# 1_NZPP.net
KiCad netlist of a schematic drawn in Altium Designer
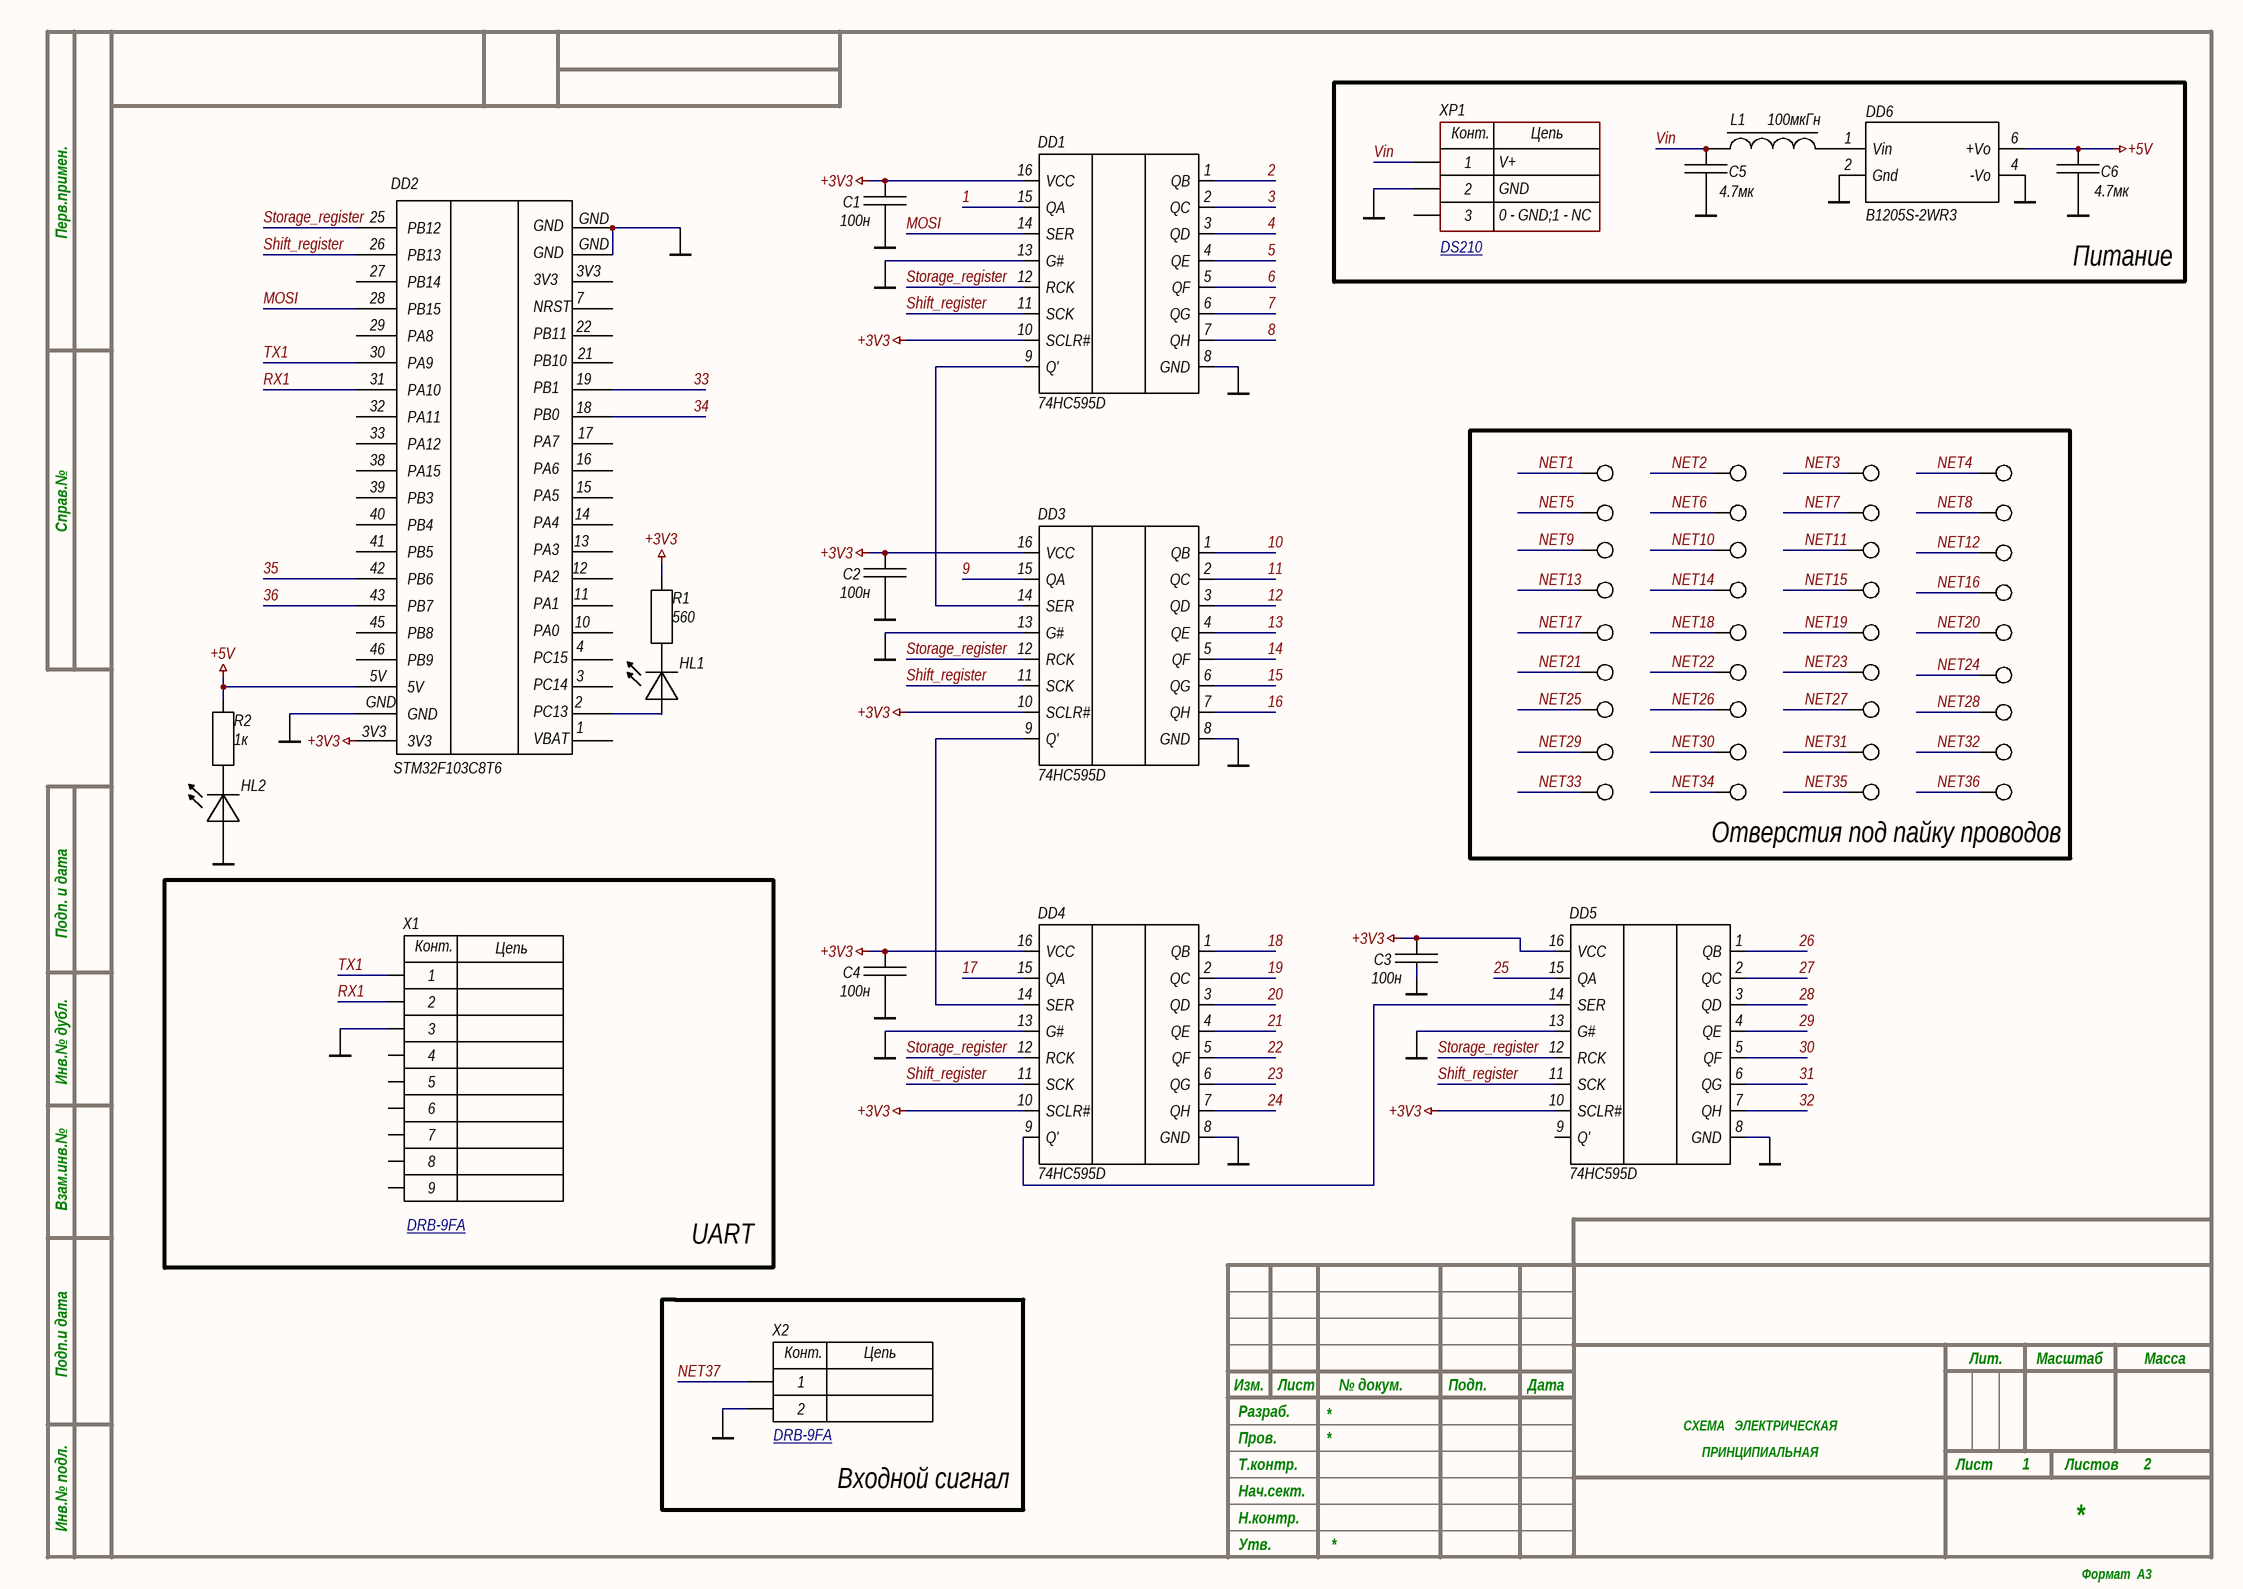
[diagram p0: 1.NZPP.SchDoc]

(export (version "E")
  (design (tool "Eeschema 10.0.6"))
  (components
    (comp (ref "*") (value "Point") (footprint "Point") (libsource (lib "Schlib1") (part "Point")))
    (comp (ref "*1") (value "Point") (footprint "Point") (libsource (lib "Schlib1") (part "Point")))
    (comp (ref "*2") (value "Point") (footprint "Point") (libsource (lib "Schlib1") (part "Point")))
    (comp (ref "*3") (value "Point") (footprint "Point") (libsource (lib "Schlib1") (part "Point")))
    (comp (ref "*4") (value "Point") (footprint "Point") (libsource (lib "Schlib1") (part "Point")))
    (comp (ref "*5") (value "Point") (footprint "Point") (libsource (lib "Schlib1") (part "Point")))
    (comp (ref "*6") (value "Point") (footprint "Point") (libsource (lib "Schlib1") (part "Point")))
    (comp (ref "*7") (value "Point") (footprint "Point") (libsource (lib "Schlib1") (part "Point")))
    (comp (ref "*8") (value "Point") (footprint "Point") (libsource (lib "Schlib1") (part "Point")))
    (comp (ref "*9") (value "Point") (footprint "Point") (libsource (lib "Schlib1") (part "Point")))
    (comp (ref "*10") (value "Point") (footprint "Point") (libsource (lib "Schlib1") (part "Point")))
    (comp (ref "*11") (value "Point") (footprint "Point") (libsource (lib "Schlib1") (part "Point")))
    (comp (ref "*12") (value "Point") (footprint "Point") (libsource (lib "Schlib1") (part "Point")))
    (comp (ref "*13") (value "Point") (footprint "Point") (libsource (lib "Schlib1") (part "Point")))
    (comp (ref "*14") (value "Point") (footprint "Point") (libsource (lib "Schlib1") (part "Point")))
    (comp (ref "*15") (value "Point") (footprint "Point") (libsource (lib "Schlib1") (part "Point")))
    (comp (ref "*16") (value "Point") (footprint "Point") (libsource (lib "Schlib1") (part "Point")))
    (comp (ref "*17") (value "Point") (footprint "Point") (libsource (lib "Schlib1") (part "Point")))
    (comp (ref "*18") (value "Point") (footprint "Point") (libsource (lib "Schlib1") (part "Point")))
    (comp (ref "*19") (value "Point") (footprint "Point") (libsource (lib "Schlib1") (part "Point")))
    (comp (ref "*20") (value "Point") (footprint "Point") (libsource (lib "Schlib1") (part "Point")))
    (comp (ref "*21") (value "Point") (footprint "Point") (libsource (lib "Schlib1") (part "Point")))
    (comp (ref "*22") (value "Point") (footprint "Point") (libsource (lib "Schlib1") (part "Point")))
    (comp (ref "*23") (value "Point") (footprint "Point") (libsource (lib "Schlib1") (part "Point")))
    (comp (ref "*24") (value "Point") (footprint "Point") (libsource (lib "Schlib1") (part "Point")))
    (comp (ref "*25") (value "Point") (footprint "Point") (libsource (lib "Schlib1") (part "Point")))
    (comp (ref "*26") (value "Point") (footprint "Point") (libsource (lib "Schlib1") (part "Point")))
    (comp (ref "*27") (value "Point") (footprint "Point") (libsource (lib "Schlib1") (part "Point")))
    (comp (ref "*28") (value "Point") (footprint "Point") (libsource (lib "Schlib1") (part "Point")))
    (comp (ref "*29") (value "Point") (footprint "Point") (libsource (lib "Schlib1") (part "Point")))
    (comp (ref "*30") (value "Point") (footprint "Point") (libsource (lib "Schlib1") (part "Point")))
    (comp (ref "*31") (value "Point") (footprint "Point") (libsource (lib "Schlib1") (part "Point")))
    (comp (ref "*32") (value "Point") (footprint "Point") (libsource (lib "Schlib1") (part "Point")))
    (comp (ref "*33") (value "Point") (footprint "Point") (libsource (lib "Schlib1") (part "Point")))
    (comp (ref "*34") (value "Point") (footprint "Point") (libsource (lib "Schlib1") (part "Point")))
    (comp (ref "*35") (value "Point") (footprint "Point") (libsource (lib "Schlib1") (part "Point")))
    (comp (ref "C1")
      (value "100н")
      (footprint "CAP: 0805")
      (libsource (lib "capacitor") (part "Ceramic_0805"))
    )
    (comp (ref "C2")
      (value "100н")
      (footprint "CAP: 0805")
      (libsource (lib "capacitor") (part "Ceramic_0805"))
    )
    (comp (ref "C3")
      (value "100н")
      (footprint "CAP: 0805")
      (libsource (lib "capacitor") (part "Ceramic_0805"))
    )
    (comp (ref "C4")
      (value "100н")
      (footprint "CAP: 0805")
      (libsource (lib "capacitor") (part "Ceramic_0805"))
    )
    (comp (ref "C5")
      (value "4.7мк")
      (footprint "CAP: 0805")
      (libsource (lib "capacitor") (part "Ceramic_0805"))
    )
    (comp (ref "C6")
      (value "4.7мк")
      (footprint "CAP: 0805")
      (libsource (lib "capacitor") (part "Ceramic_0805"))
    )
    (comp (ref "DD1") (value "74HC595D") (footprint "74HC595D") (libsource (lib "") (part "74HC595D_1")))
    (comp (ref "DD2")
      (value "STM32F103C8T6")
      (footprint "STM32F103C8T6 - duplicate")
      (libsource (lib "Schlib1") (part "STM32F103"))
    )
    (comp (ref "DD3") (value "74HC595D") (footprint "74HC595D") (libsource (lib "Schlib1") (part "74HC595D")))
    (comp (ref "DD4") (value "74HC595D") (footprint "74HC595D") (libsource (lib "Schlib1") (part "74HC595D")))
    (comp (ref "DD5") (value "74HC595D") (footprint "74HC595D") (libsource (lib "Schlib1") (part "74HC595D")))
    (comp (ref "DD6")
      (value "B1205S-2WR3")
      (footprint "B1205S-2WR3")
      (libsource (lib "Schlib1") (part "B1205S-2WR3"))
    )
    (comp (ref "HL1") (value "GNL-3012HD") (footprint "led") (libsource (lib "Schlib1") (part "LED")))
    (comp (ref "HL2") (value "GNL-3012HD") (footprint "led") (libsource (lib "Schlib1") (part "LED")))
    (comp (ref "L1")
      (value "100мкГн")
      (footprint "100мкГн")
      (libsource (lib "Schlib1") (part "Дроссель 100мкГн CD43-101K"))
    )
    (comp (ref "R1")
      (value "560")
      (footprint "RES: 0805")
      (libsource (lib "resistor") (part "Resistor_0805"))
    )
    (comp (ref "R2") (value "1к") (footprint "RES: 0805") (libsource (lib "resistor") (part "Resistor_0805")))
    (comp (ref "X1") (value "DRB-9FA") (footprint "CON: DB-9F") (libsource (lib "Schlib1") (part "DRB-9FA")))
    (comp (ref "X2")
      (value "SMA-KWHD")
      (footprint "CON: SMA-KWHD")
      (libsource (lib "Schlib1") (part "Connector_terminal_2pin"))
    )
    (comp (ref "XP1") (value "DS210") (footprint "CON: DS210") (libsource (lib "Schlib1") (part "DS210")))
  )
  (nets
    (net (code "1") (name "+3V3") (class "Default")
      (node (ref "C1") (pin "2") (pinfunction "2_2") (pintype "passive"))
      (node (ref "C2") (pin "2") (pinfunction "2_2") (pintype "passive"))
      (node (ref "C3") (pin "2") (pinfunction "2_2") (pintype "passive"))
      (node (ref "C4") (pin "2") (pinfunction "2_2") (pintype "passive"))
      (node (ref "DD1") (pin "10") (pinfunction "SCLR#_10") (pintype "passive"))
      (node (ref "DD1") (pin "16") (pinfunction "VCC_16") (pintype "passive"))
      (node (ref "DD2") (pin "A2") (pinfunction "3V3_A2") (pintype "passive"))
      (node (ref "DD3") (pin "10") (pinfunction "SCLR#_10") (pintype "passive"))
      (node (ref "DD3") (pin "16") (pinfunction "VCC_16") (pintype "passive"))
      (node (ref "DD4") (pin "10") (pinfunction "SCLR#_10") (pintype "passive"))
      (node (ref "DD4") (pin "16") (pinfunction "VCC_16") (pintype "passive"))
      (node (ref "DD5") (pin "10") (pinfunction "SCLR#_10") (pintype "passive"))
      (node (ref "DD5") (pin "16") (pinfunction "VCC_16") (pintype "passive"))
      (node (ref "R1") (pin "2") (pinfunction "2_2") (pintype "passive"))
    )
    (net (code "2") (name "+5V") (class "Default")
      (node (ref "C6") (pin "2") (pinfunction "2_2") (pintype "passive"))
      (node (ref "DD2") (pin "5V") (pinfunction "5V_5V") (pintype "passive"))
      (node (ref "DD6") (pin "6") (pinfunction "+Vo_6") (pintype "passive"))
      (node (ref "R2") (pin "2") (pinfunction "2_2") (pintype "passive"))
    )
    (net (code "3") (name "/1") (class "Default")
      (node (ref "DD1") (pin "15") (pinfunction "QA_15") (pintype "passive"))
    )
    (net (code "4") (name "/2") (class "Default")
      (node (ref "DD1") (pin "1") (pinfunction "QB_1") (pintype "passive"))
    )
    (net (code "5") (name "/3") (class "Default")
      (node (ref "DD1") (pin "2") (pinfunction "QC_2") (pintype "passive"))
    )
    (net (code "6") (name "/4") (class "Default")
      (node (ref "DD1") (pin "3") (pinfunction "QD_3") (pintype "passive"))
    )
    (net (code "7") (name "/5") (class "Default")
      (node (ref "DD1") (pin "4") (pinfunction "QE_4") (pintype "passive"))
    )
    (net (code "8") (name "/6") (class "Default")
      (node (ref "DD1") (pin "5") (pinfunction "QF_5") (pintype "passive"))
    )
    (net (code "9") (name "/7") (class "Default")
      (node (ref "DD1") (pin "6") (pinfunction "QG_6") (pintype "passive"))
    )
    (net (code "10") (name "/8") (class "Default")
      (node (ref "DD1") (pin "7") (pinfunction "QH_7") (pintype "passive"))
    )
    (net (code "11") (name "/9") (class "Default")
      (node (ref "DD3") (pin "15") (pinfunction "QA_15") (pintype "passive"))
    )
    (net (code "12") (name "/10") (class "Default")
      (node (ref "DD3") (pin "1") (pinfunction "QB_1") (pintype "passive"))
    )
    (net (code "13") (name "/11") (class "Default")
      (node (ref "DD3") (pin "2") (pinfunction "QC_2") (pintype "passive"))
    )
    (net (code "14") (name "/12") (class "Default")
      (node (ref "DD3") (pin "3") (pinfunction "QD_3") (pintype "passive"))
    )
    (net (code "15") (name "/13") (class "Default")
      (node (ref "DD3") (pin "4") (pinfunction "QE_4") (pintype "passive"))
    )
    (net (code "16") (name "/14") (class "Default")
      (node (ref "DD3") (pin "5") (pinfunction "QF_5") (pintype "passive"))
    )
    (net (code "17") (name "/15") (class "Default")
      (node (ref "DD3") (pin "6") (pinfunction "QG_6") (pintype "passive"))
    )
    (net (code "18") (name "/16") (class "Default")
      (node (ref "DD3") (pin "7") (pinfunction "QH_7") (pintype "passive"))
    )
    (net (code "19") (name "/17") (class "Default")
      (node (ref "DD4") (pin "15") (pinfunction "QA_15") (pintype "passive"))
    )
    (net (code "20") (name "/18") (class "Default")
      (node (ref "DD4") (pin "1") (pinfunction "QB_1") (pintype "passive"))
    )
    (net (code "21") (name "/19") (class "Default")
      (node (ref "DD4") (pin "2") (pinfunction "QC_2") (pintype "passive"))
    )
    (net (code "22") (name "/20") (class "Default")
      (node (ref "DD4") (pin "3") (pinfunction "QD_3") (pintype "passive"))
    )
    (net (code "23") (name "/21") (class "Default")
      (node (ref "DD4") (pin "4") (pinfunction "QE_4") (pintype "passive"))
    )
    (net (code "24") (name "/22") (class "Default")
      (node (ref "DD4") (pin "5") (pinfunction "QF_5") (pintype "passive"))
    )
    (net (code "25") (name "/23") (class "Default")
      (node (ref "DD4") (pin "6") (pinfunction "QG_6") (pintype "passive"))
    )
    (net (code "26") (name "/24") (class "Default")
      (node (ref "DD4") (pin "7") (pinfunction "QH_7") (pintype "passive"))
    )
    (net (code "27") (name "/25") (class "Default")
      (node (ref "DD5") (pin "15") (pinfunction "QA_15") (pintype "passive"))
    )
    (net (code "28") (name "/26") (class "Default")
      (node (ref "DD5") (pin "1") (pinfunction "QB_1") (pintype "passive"))
    )
    (net (code "29") (name "/27") (class "Default")
      (node (ref "DD5") (pin "2") (pinfunction "QC_2") (pintype "passive"))
    )
    (net (code "30") (name "/28") (class "Default")
      (node (ref "DD5") (pin "3") (pinfunction "QD_3") (pintype "passive"))
    )
    (net (code "31") (name "/29") (class "Default")
      (node (ref "DD5") (pin "4") (pinfunction "QE_4") (pintype "passive"))
    )
    (net (code "32") (name "/30") (class "Default")
      (node (ref "DD5") (pin "5") (pinfunction "QF_5") (pintype "passive"))
    )
    (net (code "33") (name "/31") (class "Default")
      (node (ref "DD5") (pin "6") (pinfunction "QG_6") (pintype "passive"))
    )
    (net (code "34") (name "/32") (class "Default")
      (node (ref "DD5") (pin "7") (pinfunction "QH_7") (pintype "passive"))
    )
    (net (code "35") (name "/33") (class "Default")
      (node (ref "DD2") (pin "19") (pinfunction "PB1_19") (pintype "passive"))
    )
    (net (code "36") (name "/34") (class "Default")
      (node (ref "DD2") (pin "18") (pinfunction "PB0_18") (pintype "passive"))
    )
    (net (code "37") (name "/35") (class "Default")
      (node (ref "DD2") (pin "42") (pinfunction "PB6_42") (pintype "passive"))
    )
    (net (code "38") (name "/36") (class "Default")
      (node (ref "DD2") (pin "43") (pinfunction "PB7_43") (pintype "passive"))
    )
    (net (code "39") (name "/MOSI") (class "Default")
      (node (ref "DD1") (pin "14") (pinfunction "SER_14") (pintype "passive"))
      (node (ref "DD2") (pin "28") (pinfunction "PB15_28") (pintype "passive"))
    )
    (net (code "40") (name "/NET1") (class "Default")
      (node (ref "*") (pin "1") (pinfunction "4_1") (pintype "passive"))
    )
    (net (code "41") (name "/NET2") (class "Default")
      (node (ref "*1") (pin "1") (pinfunction "4_1") (pintype "passive"))
    )
    (net (code "42") (name "/NET3") (class "Default")
      (node (ref "*2") (pin "1") (pinfunction "4_1") (pintype "passive"))
    )
    (net (code "43") (name "/NET4") (class "Default")
      (node (ref "*3") (pin "1") (pinfunction "4_1") (pintype "passive"))
    )
    (net (code "44") (name "/NET5") (class "Default")
      (node (ref "*4") (pin "1") (pinfunction "4_1") (pintype "passive"))
    )
    (net (code "45") (name "/NET6") (class "Default")
      (node (ref "*5") (pin "1") (pinfunction "4_1") (pintype "passive"))
    )
    (net (code "46") (name "/NET7") (class "Default")
      (node (ref "*6") (pin "1") (pinfunction "4_1") (pintype "passive"))
    )
    (net (code "47") (name "/NET8") (class "Default")
      (node (ref "*7") (pin "1") (pinfunction "4_1") (pintype "passive"))
    )
    (net (code "48") (name "/NET9") (class "Default")
      (node (ref "*8") (pin "1") (pinfunction "4_1") (pintype "passive"))
    )
    (net (code "49") (name "/NET10") (class "Default")
      (node (ref "*9") (pin "1") (pinfunction "4_1") (pintype "passive"))
    )
    (net (code "50") (name "/NET11") (class "Default")
      (node (ref "*10") (pin "1") (pinfunction "4_1") (pintype "passive"))
    )
    (net (code "51") (name "/NET12") (class "Default")
      (node (ref "*11") (pin "1") (pinfunction "4_1") (pintype "passive"))
    )
    (net (code "52") (name "/NET13") (class "Default")
      (node (ref "*12") (pin "1") (pinfunction "4_1") (pintype "passive"))
    )
    (net (code "53") (name "/NET14") (class "Default")
      (node (ref "*13") (pin "1") (pinfunction "4_1") (pintype "passive"))
    )
    (net (code "54") (name "/NET15") (class "Default")
      (node (ref "*14") (pin "1") (pinfunction "4_1") (pintype "passive"))
    )
    (net (code "55") (name "/NET16") (class "Default")
      (node (ref "*15") (pin "1") (pinfunction "4_1") (pintype "passive"))
    )
    (net (code "56") (name "/NET17") (class "Default")
      (node (ref "*16") (pin "1") (pinfunction "4_1") (pintype "passive"))
    )
    (net (code "57") (name "/NET18") (class "Default")
      (node (ref "*17") (pin "1") (pinfunction "4_1") (pintype "passive"))
    )
    (net (code "58") (name "/NET19") (class "Default")
      (node (ref "*18") (pin "1") (pinfunction "4_1") (pintype "passive"))
    )
    (net (code "59") (name "/NET20") (class "Default")
      (node (ref "*19") (pin "1") (pinfunction "4_1") (pintype "passive"))
    )
    (net (code "60") (name "/NET21") (class "Default")
      (node (ref "*20") (pin "1") (pinfunction "4_1") (pintype "passive"))
    )
    (net (code "61") (name "/NET22") (class "Default")
      (node (ref "*21") (pin "1") (pinfunction "4_1") (pintype "passive"))
    )
    (net (code "62") (name "/NET23") (class "Default")
      (node (ref "*22") (pin "1") (pinfunction "4_1") (pintype "passive"))
    )
    (net (code "63") (name "/NET24") (class "Default")
      (node (ref "*23") (pin "1") (pinfunction "4_1") (pintype "passive"))
    )
    (net (code "64") (name "/NET25") (class "Default")
      (node (ref "*24") (pin "1") (pinfunction "4_1") (pintype "passive"))
    )
    (net (code "65") (name "/NET26") (class "Default")
      (node (ref "*25") (pin "1") (pinfunction "4_1") (pintype "passive"))
    )
    (net (code "66") (name "/NET27") (class "Default")
      (node (ref "*26") (pin "1") (pinfunction "4_1") (pintype "passive"))
    )
    (net (code "67") (name "/NET28") (class "Default")
      (node (ref "*27") (pin "1") (pinfunction "4_1") (pintype "passive"))
    )
    (net (code "68") (name "/NET29") (class "Default")
      (node (ref "*28") (pin "1") (pinfunction "4_1") (pintype "passive"))
    )
    (net (code "69") (name "/NET30") (class "Default")
      (node (ref "*29") (pin "1") (pinfunction "4_1") (pintype "passive"))
    )
    (net (code "70") (name "/NET31") (class "Default")
      (node (ref "*30") (pin "1") (pinfunction "4_1") (pintype "passive"))
    )
    (net (code "71") (name "/NET32") (class "Default")
      (node (ref "*31") (pin "1") (pinfunction "4_1") (pintype "passive"))
    )
    (net (code "72") (name "/NET33") (class "Default")
      (node (ref "*32") (pin "1") (pinfunction "4_1") (pintype "passive"))
    )
    (net (code "73") (name "/NET34") (class "Default")
      (node (ref "*33") (pin "1") (pinfunction "4_1") (pintype "passive"))
    )
    (net (code "74") (name "/NET35") (class "Default")
      (node (ref "*34") (pin "1") (pinfunction "4_1") (pintype "passive"))
    )
    (net (code "75") (name "/NET36") (class "Default")
      (node (ref "*35") (pin "1") (pinfunction "4_1") (pintype "passive"))
    )
    (net (code "76") (name "/NET37") (class "Default")
      (node (ref "X2") (pin "1") (pinfunction "1_1") (pintype "passive"))
    )
    (net (code "77") (name "/RX1") (class "Default")
      (node (ref "DD2") (pin "31") (pinfunction "PA10_31") (pintype "passive"))
      (node (ref "X1") (pin "2") (pinfunction "2_2") (pintype "passive"))
    )
    (net (code "78") (name "/Shift_register") (class "Default")
      (node (ref "DD1") (pin "11") (pinfunction "SCK_11") (pintype "passive"))
      (node (ref "DD2") (pin "26") (pinfunction "PB13_26") (pintype "passive"))
      (node (ref "DD3") (pin "11") (pinfunction "SCK_11") (pintype "passive"))
      (node (ref "DD4") (pin "11") (pinfunction "SCK_11") (pintype "passive"))
      (node (ref "DD5") (pin "11") (pinfunction "SCK_11") (pintype "passive"))
    )
    (net (code "79") (name "/Storage_register") (class "Default")
      (node (ref "DD1") (pin "12") (pinfunction "RCK_12") (pintype "passive"))
      (node (ref "DD2") (pin "25") (pinfunction "PB12_25") (pintype "passive"))
      (node (ref "DD3") (pin "12") (pinfunction "RCK_12") (pintype "passive"))
      (node (ref "DD4") (pin "12") (pinfunction "RCK_12") (pintype "passive"))
      (node (ref "DD5") (pin "12") (pinfunction "RCK_12") (pintype "passive"))
    )
    (net (code "80") (name "/TX1") (class "Default")
      (node (ref "DD2") (pin "30") (pinfunction "PA9_30") (pintype "passive"))
      (node (ref "X1") (pin "1") (pinfunction "1_1") (pintype "passive"))
    )
    (net (code "81") (name "/Vin") (class "Default")
      (node (ref "C5") (pin "2") (pinfunction "2_2") (pintype "passive"))
      (node (ref "L1") (pin "1") (pinfunction "1_1") (pintype "passive"))
      (node (ref "XP1") (pin "1") (pinfunction "1_1") (pintype "passive"))
    )
    (net (code "82") (name "GND") (class "Default")
      (node (ref "C1") (pin "1") (pinfunction "1_1") (pintype "passive"))
      (node (ref "C2") (pin "1") (pinfunction "1_1") (pintype "passive"))
      (node (ref "C3") (pin "1") (pinfunction "1_1") (pintype "passive"))
      (node (ref "C4") (pin "1") (pinfunction "1_1") (pintype "passive"))
      (node (ref "C5") (pin "1") (pinfunction "1_1") (pintype "passive"))
      (node (ref "C6") (pin "1") (pinfunction "1_1") (pintype "passive"))
      (node (ref "DD1") (pin "13") (pinfunction "G#_13") (pintype "passive"))
      (node (ref "DD1") (pin "8") (pinfunction "GND_8") (pintype "passive"))
      (node (ref "DD2") (pin "GND") (pinfunction "GND_GND") (pintype "passive"))
      (node (ref "DD3") (pin "13") (pinfunction "G#_13") (pintype "passive"))
      (node (ref "DD3") (pin "8") (pinfunction "GND_8") (pintype "passive"))
      (node (ref "DD4") (pin "13") (pinfunction "G#_13") (pintype "passive"))
      (node (ref "DD4") (pin "8") (pinfunction "GND_8") (pintype "passive"))
      (node (ref "DD5") (pin "13") (pinfunction "G#_13") (pintype "passive"))
      (node (ref "DD5") (pin "8") (pinfunction "GND_8") (pintype "passive"))
      (node (ref "DD6") (pin "2") (pinfunction "Gnd_2") (pintype "passive"))
      (node (ref "DD6") (pin "4") (pinfunction "-Vo_4") (pintype "passive"))
      (node (ref "HL2") (pin "1") (pinfunction "A_1") (pintype "passive"))
      (node (ref "X1") (pin "3") (pinfunction "3_3") (pintype "power_in"))
      (node (ref "X2") (pin "2") (pinfunction "2_2") (pintype "passive"))
      (node (ref "XP1") (pin "2") (pinfunction "2_2") (pintype "passive"))
    )
    (net (code "83") (name "Net-(DD1-Q')") (class "Default")
      (node (ref "DD1") (pin "9") (pinfunction "Q'_9") (pintype "passive"))
      (node (ref "DD3") (pin "14") (pinfunction "SER_14") (pintype "passive"))
    )
    (net (code "84") (name "Net-(DD2-PC13)") (class "Default")
      (node (ref "DD2") (pin "2") (pinfunction "PC13_2") (pintype "passive"))
      (node (ref "HL1") (pin "1") (pinfunction "A_1") (pintype "passive"))
    )
    (net (code "85") (name "Net-(DD3-Q')") (class "Default")
      (node (ref "DD3") (pin "9") (pinfunction "Q'_9") (pintype "passive"))
      (node (ref "DD4") (pin "14") (pinfunction "SER_14") (pintype "passive"))
    )
    (net (code "86") (name "Net-(DD4-Q')") (class "Default")
      (node (ref "DD4") (pin "9") (pinfunction "Q'_9") (pintype "passive"))
      (node (ref "DD5") (pin "14") (pinfunction "SER_14") (pintype "passive"))
    )
    (net (code "87") (name "Net-(DD6-Vin)") (class "Default")
      (node (ref "DD6") (pin "1") (pinfunction "Vin_1") (pintype "passive"))
      (node (ref "L1") (pin "2") (pinfunction "2_2") (pintype "passive"))
    )
    (net (code "88") (name "Net-(HL1-C)") (class "Default")
      (node (ref "HL1") (pin "2") (pinfunction "C_2") (pintype "passive"))
      (node (ref "R1") (pin "1") (pinfunction "1_1") (pintype "passive"))
    )
    (net (code "89") (name "Net-(HL2-C)") (class "Default")
      (node (ref "HL2") (pin "2") (pinfunction "C_2") (pintype "passive"))
      (node (ref "R2") (pin "1") (pinfunction "1_1") (pintype "passive"))
    )
    (net (code "90") (name "unconnected-(DD2-3V3-PadA1)") (class "Default")
      (node (ref "DD2") (pin "A1") (pinfunction "3V3_A1") (pintype "passive"))
    )
    (net (code "91") (name "unconnected-(DD2-NRST-Pad7)") (class "Default")
      (node (ref "DD2") (pin "7") (pinfunction "NRST_7") (pintype "passive"))
    )
    (net (code "92") (name "unconnected-(DD2-PA0-Pad10)") (class "Default")
      (node (ref "DD2") (pin "10") (pinfunction "PA0_10") (pintype "passive"))
    )
    (net (code "93") (name "unconnected-(DD2-PA1-Pad11)") (class "Default")
      (node (ref "DD2") (pin "11") (pinfunction "PA1_11") (pintype "passive"))
    )
    (net (code "94") (name "unconnected-(DD2-PA2-Pad12)") (class "Default")
      (node (ref "DD2") (pin "12") (pinfunction "PA2_12") (pintype "passive"))
    )
    (net (code "95") (name "unconnected-(DD2-PA3-Pad13)") (class "Default")
      (node (ref "DD2") (pin "13") (pinfunction "PA3_13") (pintype "passive"))
    )
    (net (code "96") (name "unconnected-(DD2-PA4-Pad14)") (class "Default")
      (node (ref "DD2") (pin "14") (pinfunction "PA4_14") (pintype "passive"))
    )
    (net (code "97") (name "unconnected-(DD2-PA5-Pad15)") (class "Default")
      (node (ref "DD2") (pin "15") (pinfunction "PA5_15") (pintype "passive"))
    )
    (net (code "98") (name "unconnected-(DD2-PA6-Pad16)") (class "Default")
      (node (ref "DD2") (pin "16") (pinfunction "PA6_16") (pintype "passive"))
    )
    (net (code "99") (name "unconnected-(DD2-PA7-Pad17)") (class "Default")
      (node (ref "DD2") (pin "17") (pinfunction "PA7_17") (pintype "passive"))
    )
    (net (code "100") (name "unconnected-(DD2-PA8-Pad29)") (class "Default")
      (node (ref "DD2") (pin "29") (pinfunction "PA8_29") (pintype "passive"))
    )
    (net (code "101") (name "unconnected-(DD2-PA11-Pad32)") (class "Default")
      (node (ref "DD2") (pin "32") (pinfunction "PA11_32") (pintype "passive"))
    )
    (net (code "102") (name "unconnected-(DD2-PA12-Pad33)") (class "Default")
      (node (ref "DD2") (pin "33") (pinfunction "PA12_33") (pintype "passive"))
    )
    (net (code "103") (name "unconnected-(DD2-PA15-Pad38)") (class "Default")
      (node (ref "DD2") (pin "38") (pinfunction "PA15_38") (pintype "passive"))
    )
    (net (code "104") (name "unconnected-(DD2-PB3-Pad39)") (class "Default")
      (node (ref "DD2") (pin "39") (pinfunction "PB3_39") (pintype "passive"))
    )
    (net (code "105") (name "unconnected-(DD2-PB4-Pad40)") (class "Default")
      (node (ref "DD2") (pin "40") (pinfunction "PB4_40") (pintype "passive"))
    )
    (net (code "106") (name "unconnected-(DD2-PB5-Pad41)") (class "Default")
      (node (ref "DD2") (pin "41") (pinfunction "PB5_41") (pintype "passive"))
    )
    (net (code "107") (name "unconnected-(DD2-PB8-Pad45)") (class "Default")
      (node (ref "DD2") (pin "45") (pinfunction "PB8_45") (pintype "passive"))
    )
    (net (code "108") (name "unconnected-(DD2-PB9-Pad46)") (class "Default")
      (node (ref "DD2") (pin "46") (pinfunction "PB9_46") (pintype "passive"))
    )
    (net (code "109") (name "unconnected-(DD2-PB10-Pad21)") (class "Default")
      (node (ref "DD2") (pin "21") (pinfunction "PB10_21") (pintype "passive"))
    )
    (net (code "110") (name "unconnected-(DD2-PB11-Pad22)") (class "Default")
      (node (ref "DD2") (pin "22") (pinfunction "PB11_22") (pintype "passive"))
    )
    (net (code "111") (name "unconnected-(DD2-PB14-Pad27)") (class "Default")
      (node (ref "DD2") (pin "27") (pinfunction "PB14_27") (pintype "passive"))
    )
    (net (code "112") (name "unconnected-(DD2-PC14-Pad3)") (class "Default")
      (node (ref "DD2") (pin "3") (pinfunction "PC14_3") (pintype "passive"))
    )
    (net (code "113") (name "unconnected-(DD2-PC15-Pad4)") (class "Default")
      (node (ref "DD2") (pin "4") (pinfunction "PC15_4") (pintype "passive"))
    )
    (net (code "114") (name "unconnected-(DD2-Vbat-Pad1)") (class "Default")
      (node (ref "DD2") (pin "1") (pinfunction "Vbat_1") (pintype "passive"))
    )
    (net (code "115") (name "unconnected-(DD5-Q'-Pad9)") (class "Default")
      (node (ref "DD5") (pin "9") (pinfunction "Q'_9") (pintype "passive"))
    )
    (net (code "116") (name "unconnected-(X1-Pad4)") (class "Default")
      (node (ref "X1") (pin "4") (pinfunction "4_4") (pintype "power_in"))
    )
    (net (code "117") (name "unconnected-(X1-Pad5)") (class "Default")
      (node (ref "X1") (pin "5") (pinfunction "5_5") (pintype "power_in"))
    )
    (net (code "118") (name "unconnected-(X1-Pad6)") (class "Default")
      (node (ref "X1") (pin "6") (pinfunction "6_6") (pintype "power_in"))
    )
    (net (code "119") (name "unconnected-(X1-Pad7)") (class "Default")
      (node (ref "X1") (pin "7") (pinfunction "7_7") (pintype "power_in"))
    )
    (net (code "120") (name "unconnected-(X1-Pad8)") (class "Default")
      (node (ref "X1") (pin "8") (pinfunction "8_8") (pintype "power_in"))
    )
    (net (code "121") (name "unconnected-(X1-Pad9)") (class "Default")
      (node (ref "X1") (pin "9") (pinfunction "9_9") (pintype "power_in"))
    )
    (net (code "122") (name "unconnected-(XP1-Pad3)") (class "Default")
      (node (ref "XP1") (pin "3") (pinfunction "3_3") (pintype "passive"))
    )
  )
)
